# USBc_to_Ethernet_2_0.net
KiCad netlist of a schematic drawn in Altium Designer
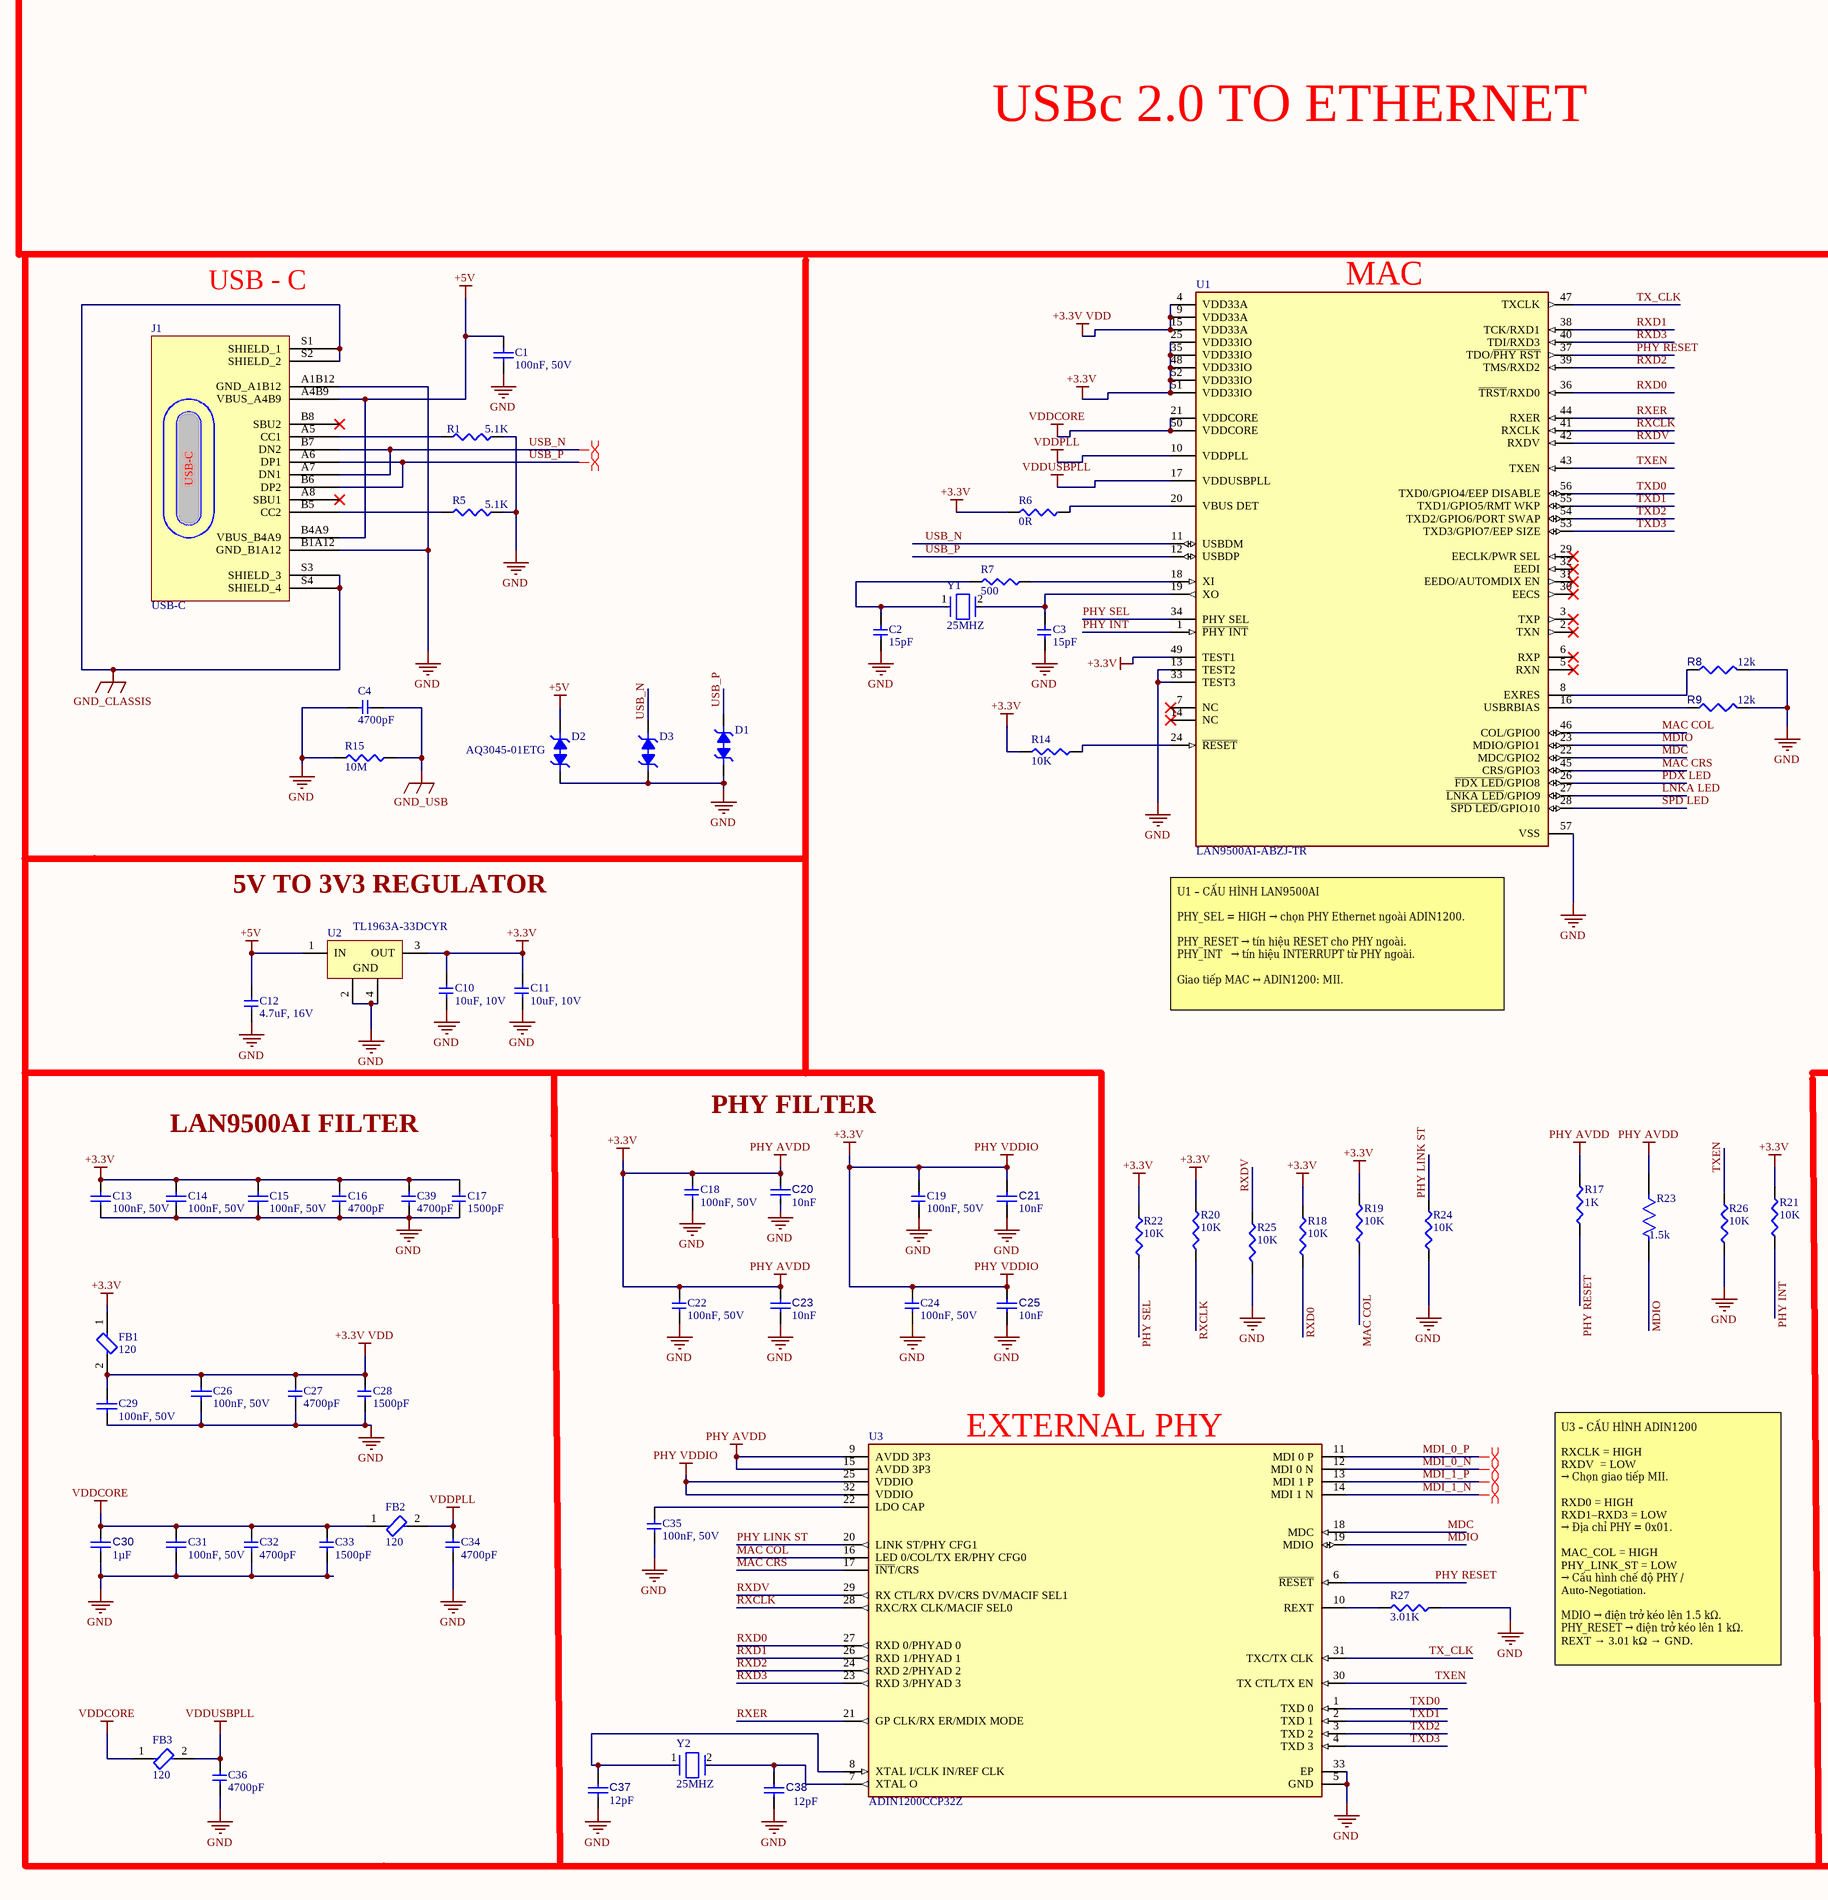
[diagram p0: USBc to Ethernet(2.0).SchDoc, left]
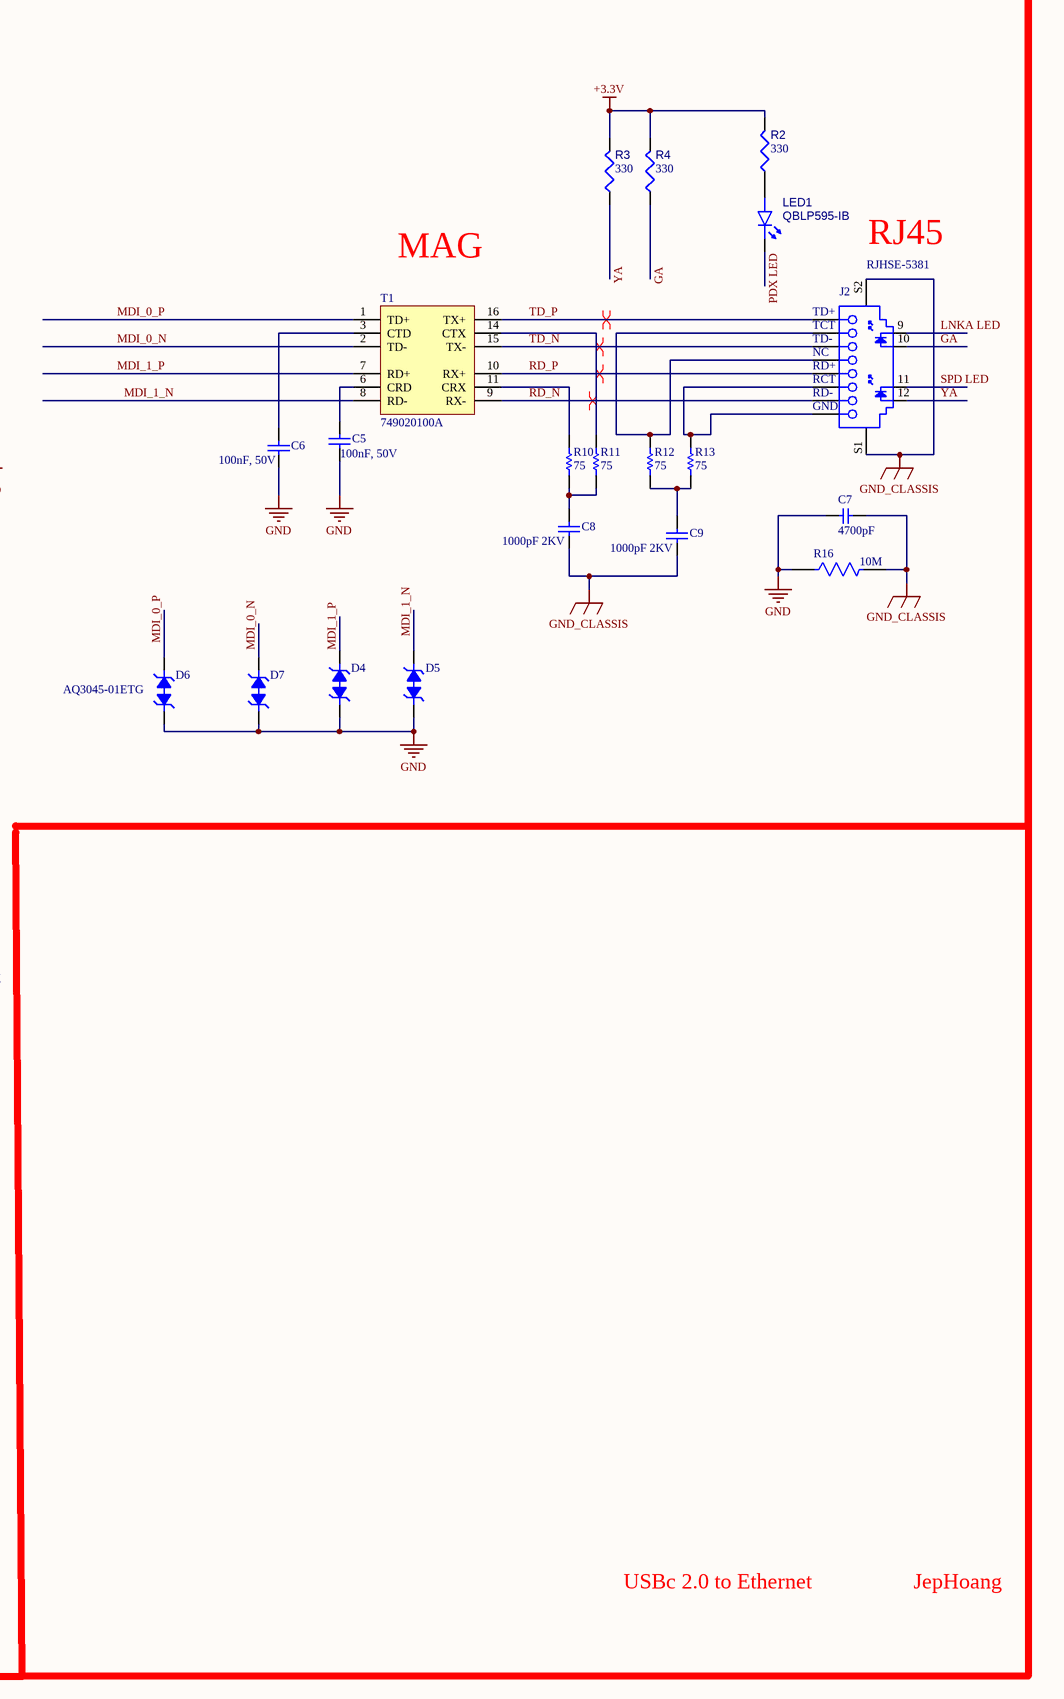
[diagram p1: USBc to Ethernet(2.0).SchDoc, right]

(export (version "E")
  (design (tool "Eeschema 10.0.6"))
  (components
    (comp (ref "C1")
      (value "100nF, 50V")
      (footprint "CAP_0402")
      (description "CAP CER 0.1UF 50V X7R 0402")
      (fields
        (field (name "MANUFACTURER") "Samsung")
        (field (name "MANUFACTURER PART NUMBER") "CL05B104KB54PNC")
      )
      (libsource (lib "HIEPSchlib") (part "CL05B104KB54PNC"))
    )
    (comp (ref "C2")
      (value "15pF")
      (footprint "CAP_0402")
      (description "Multilayer Ceramic Capacitors MLCC - SMD/SMT 0402 C0G 15pF 5% 100V automotive grade")
      (fields
        (field (name "MANUFACTURER") "Samsung Electro-Mechanics")
        (field (name "MANUFACTURER PART NUMBER") "CL05C150JC51PNC")
      )
      (libsource (lib "HIEPSchlib") (part "CL05C150JC51PNC"))
    )
    (comp (ref "C3")
      (value "15pF")
      (footprint "CAP_0402")
      (description "Multilayer Ceramic Capacitors MLCC - SMD/SMT 0402 C0G 15pF 5% 100V automotive grade")
      (fields
        (field (name "MANUFACTURER") "Samsung Electro-Mechanics")
        (field (name "MANUFACTURER PART NUMBER") "CL05C150JC51PNC")
      )
      (libsource (lib "HIEPSchlib") (part "CL05C150JC51PNC"))
    )
    (comp (ref "C4")
      (value "4700pF")
      (footprint "CAP_0402")
      (description "4700 pF ±10% 50V Ceramic Capacitor X7R 0402 (1005 Metric)")
      (fields
        (field (name "MANUFACTURER") "Samsung Electro-Mechanics")
        (field (name "MANUFACTURER PART NUMBER") "CL05B472KB5NNNC")
      )
      (libsource (lib "HIEPSchlib") (part "CL05B472KB5NNNC"))
    )
    (comp (ref "C5")
      (value "100nF, 50V")
      (footprint "CAP_0402")
      (description "CAP CER 0.1UF 50V X7R 0402")
      (fields
        (field (name "MANUFACTURER") "Samsung")
        (field (name "MANUFACTURER PART NUMBER") "CL05B104KB54PNC")
      )
      (libsource (lib "HIEPSchlib") (part "CL05B104KB54PNC"))
    )
    (comp (ref "C6")
      (value "100nF, 50V")
      (footprint "CAP_0402")
      (description "CAP CER 0.1UF 50V X7R 0402")
      (fields
        (field (name "MANUFACTURER") "Samsung")
        (field (name "MANUFACTURER PART NUMBER") "CL05B104KB54PNC")
      )
      (libsource (lib "HIEPSchlib") (part "CL05B104KB54PNC"))
    )
    (comp (ref "C7")
      (value "4700pF")
      (footprint "CAP_0402")
      (description "4700 pF ±10% 50V Ceramic Capacitor X7R 0402 (1005 Metric)")
      (fields
        (field (name "MANUFACTURER") "Samsung Electro-Mechanics")
        (field (name "MANUFACTURER PART NUMBER") "CL05B472KB5NNNC")
      )
      (libsource (lib "HIEPSchlib") (part "CL05B472KB5NNNC"))
    )
    (comp (ref "C8")
      (value "1000pF 2KV")
      (footprint "JD-202R18W102KV4E-2_M")
      (description "Chip Capacitor, 1 nF, +/- 10%, 2000 V, -55 to 125 degC, 1206 (3216 Metric), RoHS, Tape and Reel")
      (fields (field (name "MANUFACTURER") "Johanson Dielectrics") (field (name "TOLERANCE") "10%"))
      (libsource (lib "Altium Content Vault") (part "CAP-NP-2"))
    )
    (comp (ref "C9")
      (value "1000pF 2KV")
      (footprint "JD-202R18W102KV4E-2_M")
      (description "Chip Capacitor, 1 nF, +/- 10%, 2000 V, -55 to 125 degC, 1206 (3216 Metric), RoHS, Tape and Reel")
      (fields (field (name "MANUFACTURER") "Johanson Dielectrics") (field (name "TOLERANCE") "10%"))
      (libsource (lib "Altium Content Vault") (part "CAP-NP-2"))
    )
    (comp (ref "C10")
      (value "10uF, 10V")
      (footprint "CAP_0402")
      (description "CAP CER 10UF 10V X5R 0402")
      (fields
        (field (name "MANUFACTURER") "Samsung Electro-Mechanics")
        (field (name "MANUFACTURER PART NUMBER") "CL05A106MP5NUNC")
      )
      (libsource (lib "HIEPSchlib") (part "CL05A106MP5NUNC"))
    )
    (comp (ref "C11")
      (value "10uF, 10V")
      (footprint "CAP_0402")
      (description "CAP CER 10UF 10V X5R 0402")
      (fields
        (field (name "MANUFACTURER") "Samsung Electro-Mechanics")
        (field (name "MANUFACTURER PART NUMBER") "CL05A106MP5NUNC")
      )
      (libsource (lib "HIEPSchlib") (part "CL05A106MP5NUNC"))
    )
    (comp (ref "C12")
      (value "4.7uF, 16V")
      (footprint "CAP_0402")
      (description "CAP CER 4.7UF 16V X5R 0402")
      (fields
        (field (name "MANUFACTURER") "Samsung Electro-Mechanics")
        (field (name "MANUFACTURER PART NUMBER") "CL05A475MO5NUNC")
      )
      (libsource (lib "HIEPSchlib") (part "CL05A475MO5NUNC"))
    )
    (comp (ref "C13")
      (value "100nF, 50V")
      (footprint "CAP_0402")
      (description "CAP CER 0.1UF 50V X7R 0402")
      (fields
        (field (name "MANUFACTURER") "Samsung")
        (field (name "MANUFACTURER PART NUMBER") "CL05B104KB54PNC")
      )
      (libsource (lib "HIEPSchlib") (part "CL05B104KB54PNC"))
    )
    (comp (ref "C14")
      (value "100nF, 50V")
      (footprint "CAP_0402")
      (description "CAP CER 0.1UF 50V X7R 0402")
      (fields
        (field (name "MANUFACTURER") "Samsung")
        (field (name "MANUFACTURER PART NUMBER") "CL05B104KB54PNC")
      )
      (libsource (lib "HIEPSchlib") (part "CL05B104KB54PNC"))
    )
    (comp (ref "C15")
      (value "100nF, 50V")
      (footprint "CAP_0402")
      (description "CAP CER 0.1UF 50V X7R 0402")
      (fields
        (field (name "MANUFACTURER") "Samsung")
        (field (name "MANUFACTURER PART NUMBER") "CL05B104KB54PNC")
      )
      (libsource (lib "HIEPSchlib") (part "CL05B104KB54PNC"))
    )
    (comp (ref "C16")
      (value "4700pF")
      (footprint "CAP_0402")
      (description "4700 pF ±10% 50V Ceramic Capacitor X7R 0402 (1005 Metric)")
      (fields
        (field (name "MANUFACTURER") "Samsung Electro-Mechanics")
        (field (name "MANUFACTURER PART NUMBER") "CL05B472KB5NNNC")
      )
      (libsource (lib "HIEPSchlib") (part "CL05B472KB5NNNC"))
    )
    (comp (ref "C17")
      (value "1500pF")
      (footprint "CAP_0402")
      (description "1500 pF ±10% 50V Ceramic Capacitor X7R 0402 (1005 Metric)")
      (fields
        (field (name "MANUFACTURER") "Samsung Electro-Mechanics")
        (field (name "MANUFACTURER PART NUMBER") "CL05B152KB5VPNC")
      )
      (libsource (lib "HIEPSchlib") (part "CL05B152KB5VPNC"))
    )
    (comp (ref "C18")
      (value "100nF, 50V")
      (footprint "CAP_0402")
      (description "Multilayer Ceramic Capacitors MLCC - SMD/SMT 100nF0.150V X7R 1005 0402")
      (fields
        (field (name "MANUFACTURER") "Samsung Electro-Mechanics")
        (field (name "MANUFACTURER PART NUMBER") "CL05B104KB5NNNC")
      )
      (libsource (lib "HIEPSchlib") (part "CL05B104KB5NNNC"))
    )
    (comp (ref "C19")
      (value "100nF, 50V")
      (footprint "CAP_0402")
      (description "Multilayer Ceramic Capacitors MLCC - SMD/SMT 100nF0.150V X7R 1005 0402")
      (fields
        (field (name "MANUFACTURER") "Samsung Electro-Mechanics")
        (field (name "MANUFACTURER PART NUMBER") "CL05B104KB5NNNC")
      )
      (libsource (lib "HIEPSchlib") (part "CL05B104KB5NNNC"))
    )
    (comp (ref "C20")
      (value "10nF")
      (footprint "CAPC0402(1005)60_L")
      (description "Chip Capacitor, 10nF +/-20%, 50V, 0402, Thickness 0.6 mm")
      (fields (field (name "TOLERANCE") "5%") (field (name "Comment") "Capacitor 10nF +/-20% 50V 0402"))
      (libsource (lib "Hiep Hoang") (part "CAP-NP-2"))
    )
    (comp (ref "C21")
      (value "10nF")
      (footprint "CAPC0402(1005)60_L")
      (description "Chip Capacitor, 10nF +/-20%, 50V, 0402, Thickness 0.6 mm")
      (fields (field (name "TOLERANCE") "5%") (field (name "Comment") "Capacitor 10nF +/-20% 50V 0402"))
      (libsource (lib "Hiep Hoang") (part "CAP-NP-2"))
    )
    (comp (ref "C22")
      (value "100nF, 50V")
      (footprint "CAP_0402")
      (description "Multilayer Ceramic Capacitors MLCC - SMD/SMT 100nF0.150V X7R 1005 0402")
      (fields
        (field (name "MANUFACTURER") "Samsung Electro-Mechanics")
        (field (name "MANUFACTURER PART NUMBER") "CL05B104KB5NNNC")
      )
      (libsource (lib "HIEPSchlib") (part "CL05B104KB5NNNC"))
    )
    (comp (ref "C23")
      (value "10nF")
      (footprint "CAPC0402(1005)60_L")
      (description "Chip Capacitor, 10nF +/-20%, 50V, 0402, Thickness 0.6 mm")
      (fields (field (name "TOLERANCE") "5%") (field (name "Comment") "Capacitor 10nF +/-20% 50V 0402"))
      (libsource (lib "Hiep Hoang") (part "CAP-NP-2"))
    )
    (comp (ref "C24")
      (value "100nF, 50V")
      (footprint "CAP_0402")
      (description "Multilayer Ceramic Capacitors MLCC - SMD/SMT 100nF0.150V X7R 1005 0402")
      (fields
        (field (name "MANUFACTURER") "Samsung Electro-Mechanics")
        (field (name "MANUFACTURER PART NUMBER") "CL05B104KB5NNNC")
      )
      (libsource (lib "HIEPSchlib") (part "CL05B104KB5NNNC"))
    )
    (comp (ref "C25")
      (value "10nF")
      (footprint "CAPC0402(1005)60_L")
      (description "Chip Capacitor, 10nF +/-20%, 50V, 0402, Thickness 0.6 mm")
      (fields (field (name "TOLERANCE") "5%") (field (name "Comment") "Capacitor 10nF +/-20% 50V 0402"))
      (libsource (lib "Hiep Hoang") (part "CAP-NP-2"))
    )
    (comp (ref "C26")
      (value "100nF, 50V")
      (footprint "CAP_0402")
      (description "CAP CER 0.1UF 50V X7R 0402")
      (fields
        (field (name "MANUFACTURER") "Samsung")
        (field (name "MANUFACTURER PART NUMBER") "CL05B104KB54PNC")
      )
      (libsource (lib "HIEPSchlib") (part "CL05B104KB54PNC"))
    )
    (comp (ref "C27")
      (value "4700pF")
      (footprint "CAP_0402")
      (description "4700 pF ±10% 50V Ceramic Capacitor X7R 0402 (1005 Metric)")
      (fields
        (field (name "MANUFACTURER") "Samsung Electro-Mechanics")
        (field (name "MANUFACTURER PART NUMBER") "CL05B472KB5NNNC")
      )
      (libsource (lib "HIEPSchlib") (part "CL05B472KB5NNNC"))
    )
    (comp (ref "C28")
      (value "1500pF")
      (footprint "CAP_0402")
      (description "1500 pF ±10% 50V Ceramic Capacitor X7R 0402 (1005 Metric)")
      (fields
        (field (name "MANUFACTURER") "Samsung Electro-Mechanics")
        (field (name "MANUFACTURER PART NUMBER") "CL05B152KB5VPNC")
      )
      (libsource (lib "HIEPSchlib") (part "CL05B152KB5VPNC"))
    )
    (comp (ref "C29")
      (value "100nF, 50V")
      (footprint "CAP_0402")
      (description "CAP CER 0.1UF 50V X7R 0402")
      (fields
        (field (name "MANUFACTURER") "Samsung")
        (field (name "MANUFACTURER PART NUMBER") "CL05B104KB54PNC")
      )
      (libsource (lib "HIEPSchlib") (part "CL05B104KB54PNC"))
    )
    (comp (ref "C30")
      (value "1µF")
      (footprint "CAPC0402(1005)60_L")
      (description "Chip Capacitor, 1µF +/-20%, 10V, 0402, Thickness 0.6 mm")
      (fields (field (name "TOLERANCE") "10%") (field (name "Comment") "Capacitor 1µF +/-20% 10V 0402"))
      (libsource (lib "Hiep Hoang") (part "CAP-NP-2"))
    )
    (comp (ref "C31")
      (value "100nF, 50V")
      (footprint "CAP_0402")
      (description "CAP CER 0.1UF 50V X7R 0402")
      (fields
        (field (name "MANUFACTURER") "Samsung")
        (field (name "MANUFACTURER PART NUMBER") "CL05B104KB54PNC")
      )
      (libsource (lib "HIEPSchlib") (part "CL05B104KB54PNC"))
    )
    (comp (ref "C32")
      (value "4700pF")
      (footprint "CAP_0402")
      (description "4700 pF ±10% 50V Ceramic Capacitor X7R 0402 (1005 Metric)")
      (fields
        (field (name "MANUFACTURER") "Samsung Electro-Mechanics")
        (field (name "MANUFACTURER PART NUMBER") "CL05B472KB5NNNC")
      )
      (libsource (lib "HIEPSchlib") (part "CL05B472KB5NNNC"))
    )
    (comp (ref "C33")
      (value "1500pF")
      (footprint "CAP_0402")
      (description "1500 pF ±10% 50V Ceramic Capacitor X7R 0402 (1005 Metric)")
      (fields
        (field (name "MANUFACTURER") "Samsung Electro-Mechanics")
        (field (name "MANUFACTURER PART NUMBER") "CL05B152KB5VPNC")
      )
      (libsource (lib "HIEPSchlib") (part "CL05B152KB5VPNC"))
    )
    (comp (ref "C34")
      (value "4700pF")
      (footprint "CAP_0402")
      (description "4700 pF ±10% 50V Ceramic Capacitor X7R 0402 (1005 Metric)")
      (fields
        (field (name "MANUFACTURER") "Samsung Electro-Mechanics")
        (field (name "MANUFACTURER PART NUMBER") "CL05B472KB5NNNC")
      )
      (libsource (lib "HIEPSchlib") (part "CL05B472KB5NNNC"))
    )
    (comp (ref "C35")
      (value "100nF, 50V")
      (footprint "CAP_0402")
      (description "Multilayer Ceramic Capacitors MLCC - SMD/SMT 100nF0.150V X7R 1005 0402")
      (fields
        (field (name "MANUFACTURER") "Samsung Electro-Mechanics")
        (field (name "MANUFACTURER PART NUMBER") "CL05B104KB5NNNC")
      )
      (libsource (lib "HIEPSchlib") (part "CL05B104KB5NNNC"))
    )
    (comp (ref "C36")
      (value "4700pF")
      (footprint "CAP_0402")
      (description "4700 pF ±10% 50V Ceramic Capacitor X7R 0402 (1005 Metric)")
      (fields
        (field (name "MANUFACTURER") "Samsung Electro-Mechanics")
        (field (name "MANUFACTURER PART NUMBER") "CL05B472KB5NNNC")
      )
      (libsource (lib "HIEPSchlib") (part "CL05B472KB5NNNC"))
    )
    (comp (ref "C37")
      (value "12pF")
      (footprint "CAPC0402(1005)33_L")
      (description "Chip Capacitor, 12pF +/-10%, 50V, 0402, Thickness 0.33 mm")
      (fields (field (name "TOLERANCE") "20%") (field (name "Comment") "Capacitor 12pF +/-10% 50V 0402"))
      (libsource (lib "Hiep Hoang") (part "CAP-NP-2"))
    )
    (comp (ref "C38")
      (value "12pF")
      (footprint "CAPC0402(1005)33_L")
      (description "Chip Capacitor, 12pF +/-10%, 50V, 0402, Thickness 0.33 mm")
      (fields (field (name "TOLERANCE") "20%") (field (name "Comment") "Capacitor 12pF +/-10% 50V 0402"))
      (libsource (lib "Hiep Hoang") (part "CAP-NP-2"))
    )
    (comp (ref "C39")
      (value "4700pF")
      (footprint "CAP_0402")
      (description "4700 pF ±10% 50V Ceramic Capacitor X7R 0402 (1005 Metric)")
      (fields
        (field (name "MANUFACTURER") "Samsung Electro-Mechanics")
        (field (name "MANUFACTURER PART NUMBER") "CL05B472KB5NNNC")
      )
      (libsource (lib "HIEPSchlib") (part "CL05B472KB5NNNC"))
    )
    (comp (ref "D1")
      (value "~")
      (footprint "DIODE_0402")
      (description "TVS DIODE 5.3VWM 12VC SOD882")
      (fields
        (field (name "MANUFACTURER") "Littelfuse")
        (field (name "MANUFACTURER PART NUMBER") "AQ3045-01ETG")
      )
      (libsource (lib "HIEPSchlib") (part "AQ3045-01ETG"))
    )
    (comp (ref "D2")
      (value "AQ3045-01ETG")
      (footprint "DIODE_0402")
      (description "TVS DIODE 5.3VWM 12VC SOD882")
      (fields (field (name "MANUFACTURER") "Littelfuse") (field (name "LCSC PART NUMBER") "C3710326"))
      (libsource (lib "HIEPSchlib") (part "AQ3045-01ETG"))
    )
    (comp (ref "D3")
      (value "~")
      (footprint "DIODE_0402")
      (description "TVS DIODE 5.3VWM 12VC SOD882")
      (fields
        (field (name "MANUFACTURER") "Littelfuse")
        (field (name "MANUFACTURER PART NUMBER") "AQ3045-01ETG")
      )
      (libsource (lib "HIEPSchlib") (part "AQ3045-01ETG"))
    )
    (comp (ref "D4")
      (value "~")
      (footprint "DIODE_0402")
      (description "TVS DIODE 5.3VWM 12VC SOD882")
      (fields
        (field (name "MANUFACTURER") "Littelfuse")
        (field (name "MANUFACTURER PART NUMBER") "AQ3045-01ETG")
      )
      (libsource (lib "HIEPSchlib") (part "AQ3045-01ETG"))
    )
    (comp (ref "D5")
      (value "~")
      (footprint "DIODE_0402")
      (description "TVS DIODE 5.3VWM 12VC SOD882")
      (fields
        (field (name "MANUFACTURER") "Littelfuse")
        (field (name "MANUFACTURER PART NUMBER") "AQ3045-01ETG")
      )
      (libsource (lib "HIEPSchlib") (part "AQ3045-01ETG"))
    )
    (comp (ref "D6")
      (value "AQ3045-01ETG")
      (footprint "DIODE_0402")
      (description "TVS DIODE 5.3VWM 12VC SOD882")
      (fields (field (name "MANUFACTURER") "Littelfuse") (field (name "LCSC PART NUMBER") "C3710326"))
      (libsource (lib "HIEPSchlib") (part "AQ3045-01ETG"))
    )
    (comp (ref "D7")
      (value "~")
      (footprint "DIODE_0402")
      (description "TVS DIODE 5.3VWM 12VC SOD882")
      (fields
        (field (name "MANUFACTURER") "Littelfuse")
        (field (name "MANUFACTURER PART NUMBER") "AQ3045-01ETG")
      )
      (libsource (lib "HIEPSchlib") (part "AQ3045-01ETG"))
    )
    (comp (ref "FB1")
      (value "120")
      (footprint "RES_0603")
      (description "FERRITE BEAD 120 OHM 0603 1LN")
      (fields
        (field (name "MANUFACTURER") "TDK")
        (field (name "MANUFACTURER PART NUMBER") "MMZ1608B121CTAH0")
      )
      (libsource (lib "HIEPSchlib") (part "MMZ1608B121CTAH0"))
    )
    (comp (ref "FB2")
      (value "120")
      (footprint "RES_0603")
      (description "FERRITE BEAD 120 OHM 0603 1LN")
      (fields
        (field (name "MANUFACTURER") "TDK")
        (field (name "MANUFACTURER PART NUMBER") "MMZ1608B121CTAH0")
      )
      (libsource (lib "HIEPSchlib") (part "MMZ1608B121CTAH0"))
    )
    (comp (ref "FB3")
      (value "120")
      (footprint "RES_0603")
      (description "FERRITE BEAD 120 OHM 0603 1LN")
      (fields
        (field (name "MANUFACTURER") "TDK")
        (field (name "MANUFACTURER PART NUMBER") "MMZ1608B121CTAH0")
      )
      (libsource (lib "HIEPSchlib") (part "MMZ1608B121CTAH0"))
    )
    (comp (ref "J1")
      (value "USB-C")
      (footprint "USBc_16PIN_QFN__footprint")
      (fields (field (name "MANUFACTURER") "Molex") (field (name "MANUFACTURER PART NUMBER") "217179-0001"))
      (libsource (lib "HIEPSchlib") (part "217179-0001"))
    )
    (comp (ref "J2")
      (value "RJHSE-5381")
      (footprint "AMPH-RJHSE-5381_V")
      (fields (field (name "MANUFACTURER") "Amphenol"))
      (libsource (lib "Altium Content Vault") (part "RJ45-12-2SHLD"))
    )
    (comp (ref "LED1")
      (value "QBLP595-IB")
      (footprint "QTB-QBLP595_V")
      (description "Chip LED 0402, Blue, 0.02 A, 3.1 to 3.7 V, -40 to 80 degC, 2-Pin SMD, RoHS, Tape and Reel")
      (libsource (lib "Hiep Hoang") (part "LED-KA-2"))
    )
    (comp (ref "R1")
      (value "5.1K")
      (footprint "RES_0402")
      (fields
        (field (name "MANUFACTURER") "Yageo Group")
        (field (name "MANUFACTURER PART NUMBER") "AF0402FR-075K1L")
        (field (name "TOLERANCE") "1%")
      )
      (libsource (lib "HIEPSchlib") (part "AF0402FR-075K1L"))
    )
    (comp (ref "R2")
      (value "330")
      (footprint "RESC0402(1005)_L")
      (description "Chip Resistor, 330 Ohms, +/-5 %, 63 mW, -55 to 155 degC, 0402")
      (fields (field (name "POWER") "63mW") (field (name "TOLERANCE") "5%"))
      (libsource (lib "Hiep Hoang") (part "RES-2"))
    )
    (comp (ref "R3")
      (value "330")
      (footprint "RESC0402(1005)_L")
      (description "Chip Resistor, 330 Ohms, +/-5 %, 63 mW, -55 to 155 degC, 0402")
      (fields (field (name "POWER") "63mW") (field (name "TOLERANCE") "5%"))
      (libsource (lib "Hiep Hoang") (part "RES-2"))
    )
    (comp (ref "R4")
      (value "330")
      (footprint "RESC0402(1005)_L")
      (description "Chip Resistor, 330 Ohms, +/-5 %, 63 mW, -55 to 155 degC, 0402")
      (fields (field (name "POWER") "63mW") (field (name "TOLERANCE") "5%"))
      (libsource (lib "Hiep Hoang") (part "RES-2"))
    )
    (comp (ref "R5")
      (value "5.1K")
      (footprint "RES_0402")
      (fields
        (field (name "MANUFACTURER") "Yageo Group")
        (field (name "MANUFACTURER PART NUMBER") "AF0402FR-075K1L")
        (field (name "TOLERANCE") "1%")
      )
      (libsource (lib "HIEPSchlib") (part "AF0402FR-075K1L"))
    )
    (comp (ref "R6")
      (value "0R")
      (footprint "RES_0402")
      (description "RES 0 OHM JUMPER 1/16W 0402")
      (fields
        (field (name "MANUFACTURER") "Yageo")
        (field (name "MANUFACTURER PART NUMBER") "RC0402JR-070RL")
      )
      (libsource (lib "HIEPSchlib") (part "RC0402JR-070RL"))
    )
    (comp (ref "R7")
      (value "500")
      (footprint "RES_0402")
      (description "500 Ohms 1% 0.063W, 1/16W Chip Resistor 0402 (1005 Metric) Moisture Resistant")
      (fields
        (field (name "MANUFACTURER") "Yageo Group")
        (field (name "MANUFACTURER PART NUMBER") "RT0402FRE07500RL")
      )
      (libsource (lib "HIEPSchlib") (part "RT0402FRE07500RL"))
    )
    (comp (ref "R8")
      (value "12k")
      (footprint "RESC0402(1005)_L")
      (description "12K 0.063W 1% 0402 (1005 Metric)  SMD")
      (fields (field (name "TOLERANCE") "1%") (field (name "POWER") "63mW"))
      (libsource (lib "Hiep Hoang") (part "12KR2F"))
    )
    (comp (ref "R9")
      (value "12k")
      (footprint "RESC0402(1005)_L")
      (description "12K 0.063W 1% 0402 (1005 Metric)  SMD")
      (fields (field (name "TOLERANCE") "1%") (field (name "POWER") "63mW"))
      (libsource (lib "Hiep Hoang") (part "12KR2F"))
    )
    (comp (ref "R10")
      (value "75")
      (footprint "RESC1005X40X25LL05T10")
      (fields (field (name "MANUFACTURER") "Yageo / Phycomp") (field (name "PART NUMBER") "RC0402FR-0775RL"))
      (libsource (lib "Altium Content Vault") (part "RES"))
    )
    (comp (ref "R11")
      (value "75")
      (footprint "RESC1005X40X25LL05T10")
      (fields (field (name "MANUFACTURER") "Yageo / Phycomp") (field (name "PART NUMBER") "RC0402FR-0775RL"))
      (libsource (lib "Altium Content Vault") (part "RES"))
    )
    (comp (ref "R12")
      (value "75")
      (footprint "RESC1005X40X25LL05T10")
      (fields (field (name "MANUFACTURER") "Yageo / Phycomp") (field (name "PART NUMBER") "RC0402FR-0775RL"))
      (libsource (lib "Altium Content Vault") (part "RES"))
    )
    (comp (ref "R13")
      (value "75")
      (footprint "RESC1005X40X25LL05T10")
      (fields (field (name "MANUFACTURER") "Yageo / Phycomp") (field (name "PART NUMBER") "RC0402FR-0775RL"))
      (libsource (lib "Altium Content Vault") (part "RES"))
    )
    (comp (ref "R14")
      (value "10K")
      (footprint "RES_0402")
      (description "RES SMD 10K OHM 1% 1/16W 0402")
      (fields
        (field (name "MANUFACTURER") "Yageo Group")
        (field (name "MANUFACTURER PART NUMBER") "AC0402FR-0710KL")
      )
      (libsource (lib "HIEPSchlib") (part "AC0402FR-0710KL"))
    )
    (comp (ref "R15")
      (value "10M")
      (footprint "RES_0603")
      (description "Res Thick Film 0603 10M Ohm 1% 0.1W(1/10W) ±100ppm/C Pad SMD T/R Automotive AEC-Q200")
      (fields
        (field (name "MANUFACTURER") "Yageo Group")
        (field (name "MANUFACTURER PART NUMBER") "AC0603FR-0710ML")
      )
      (libsource (lib "HIEPSchlib") (part "AC0603FR-0710ML"))
    )
    (comp (ref "R16")
      (value "10M")
      (footprint "FP-CRCW0603-e3-IPC_A")
      (description "RES Thick Film, 10MΩ, 1%, 0.1W, 100ppm/°C, 0603")
      (fields (field (name "TOLERANCE") "1%"))
      (libsource (lib "Altium Content Vault") (part "1029c3af85768c4190bb7ad29bc67b5"))
    )
    (comp (ref "R17")
      (value "1K")
      (footprint "RES_0402")
      (description "RES 1K OHM 1% 1/16W 0402")
      (fields
        (field (name "MANUFACTURER") "Yageo")
        (field (name "MANUFACTURER PART NUMBER") "RC0402FR-071KL")
      )
      (libsource (lib "HIEPSchlib") (part "RC0402FR-071KL"))
    )
    (comp (ref "R18")
      (value "10K")
      (footprint "RES_0402")
      (description "RES SMD 10K OHM 1% 1/16W 0402")
      (fields
        (field (name "MANUFACTURER") "Yageo Group")
        (field (name "MANUFACTURER PART NUMBER") "AC0402FR-0710KL")
      )
      (libsource (lib "HIEPSchlib") (part "AC0402FR-0710KL"))
    )
    (comp (ref "R19")
      (value "10K")
      (footprint "RES_0402")
      (description "RES SMD 10K OHM 1% 1/16W 0402")
      (fields
        (field (name "MANUFACTURER") "Yageo Group")
        (field (name "MANUFACTURER PART NUMBER") "AC0402FR-0710KL")
      )
      (libsource (lib "HIEPSchlib") (part "AC0402FR-0710KL"))
    )
    (comp (ref "R20")
      (value "10K")
      (footprint "RES_0402")
      (description "RES SMD 10K OHM 1% 1/16W 0402")
      (fields
        (field (name "MANUFACTURER") "Yageo Group")
        (field (name "MANUFACTURER PART NUMBER") "AC0402FR-0710KL")
      )
      (libsource (lib "HIEPSchlib") (part "AC0402FR-0710KL"))
    )
    (comp (ref "R21")
      (value "10K")
      (footprint "RES_0402")
      (description "RES SMD 10K OHM 1% 1/16W 0402")
      (fields
        (field (name "MANUFACTURER") "Yageo Group")
        (field (name "MANUFACTURER PART NUMBER") "AC0402FR-0710KL")
      )
      (libsource (lib "HIEPSchlib") (part "AC0402FR-0710KL"))
    )
    (comp (ref "R22")
      (value "10K")
      (footprint "RES_0402")
      (description "RES SMD 10K OHM 1% 1/16W 0402")
      (fields
        (field (name "MANUFACTURER") "Yageo Group")
        (field (name "MANUFACTURER PART NUMBER") "AC0402FR-0710KL")
      )
      (libsource (lib "HIEPSchlib") (part "AC0402FR-0710KL"))
    )
    (comp (ref "R23")
      (value "1.5k")
      (footprint "FP-RT0402-MFG")
      (description "RES SMD 1.5K OHM 0.5% 1/16W 0402")
      (fields
        (field (name "OCTOPART") "https://octopart.com/rt0402drd071k5l-yageo-1260316")
        (field (name "MANUFACTURER") "Yageo")
      )
      (libsource (lib "Altium Content Vault") (part "1029c3af85768c4190bb7ad29bc67b5"))
    )
    (comp (ref "R24")
      (value "10K")
      (footprint "RES_0402")
      (description "RES SMD 10K OHM 1% 1/16W 0402")
      (fields
        (field (name "MANUFACTURER") "Yageo Group")
        (field (name "MANUFACTURER PART NUMBER") "AC0402FR-0710KL")
      )
      (libsource (lib "HIEPSchlib") (part "AC0402FR-0710KL"))
    )
    (comp (ref "R25")
      (value "10K")
      (footprint "RES_0402")
      (description "RES SMD 10K OHM 1% 1/16W 0402")
      (fields
        (field (name "MANUFACTURER") "Yageo Group")
        (field (name "MANUFACTURER PART NUMBER") "AC0402FR-0710KL")
      )
      (libsource (lib "HIEPSchlib") (part "AC0402FR-0710KL"))
    )
    (comp (ref "R26")
      (value "10K")
      (footprint "RES_0402")
      (description "RES SMD 10K OHM 1% 1/16W 0402")
      (fields
        (field (name "MANUFACTURER") "Yageo Group")
        (field (name "MANUFACTURER PART NUMBER") "AC0402FR-0710KL")
      )
      (libsource (lib "HIEPSchlib") (part "AC0402FR-0710KL"))
    )
    (comp (ref "R27")
      (value "3.01K")
      (footprint "RES_0402")
      (description "Res Thick Film 0402 3.01K Ohm 1% 1/16W ±100ppm/°C Molded SMD Paper T/R")
      (fields
        (field (name "MANUFACTURER") "Yageo Group")
        (field (name "MANUFACTURER PART NUMBER") "RC0402FR-073K01L")
      )
      (libsource (lib "HIEPSchlib") (part "RC0402FR-073K01L"))
    )
    (comp (ref "T1")
      (value "749020100A")
      (footprint "749020100A")
      (description "Xfmr, 10/100/1000 Base-T, 0.5 Port, Smd Rohs Compliant: Yes")
      (libsource (lib "Altium Content Vault") (part "749020100A"))
    )
    (comp (ref "U1")
      (value "LAN9500AI-ABZJ-TR")
      (footprint "FP-56QFN-5904-8x8B-MFG")
      (description "Ethernet Bridge, USB to Ethernet USB 2.0, 10/100 Base-T/TX PHY USB Interface 56-QFN (8x8)")
      (fields (field (name "MANUFACTURER") "Microchip"))
      (libsource (lib "USBc to Ethernet(2.0)") (part "LAN9500AI-ABZJ-TR"))
    )
    (comp (ref "U2")
      (value "TL1963A-33DCYR")
      (footprint "Regulator_4PIN")
      (description "IC REG LINEAR 3.3V 1.5A SOT223-4")
      (fields (field (name "MANUFACTURER") "Texas Instruments") (field (name "LCSC PART NUMBER") "C181262"))
      (libsource (lib "HIEPSchlib") (part "TL1963A-33DCYR_1"))
    )
    (comp (ref "U3")
      (value "ADIN1200CCP32Z")
      (footprint "FP-CP-32-31-MFG")
      (description "INDUSTRIAL ETHERNET GIGABIT PHY")
      (fields
        (field (name "OCTOPART") "https://octopart.com/adin1200ccp32z-analog+devices-103760365")
        (field (name "MANUFACTURER") "Analog Devices")
      )
      (libsource (lib "Altium Content Vault") (part "d941291fc6595d66c86e278ecb134d7"))
    )
    (comp (ref "Y1")
      (value "25MHZ")
      (footprint "Crystal_25MHZ")
      (description "Parallel - Fundamental Quartz Crystal, 25MHz Nom")
      (fields
        (field (name "MANUFACTURER") "CTS Components")
        (field (name "MANUFACTURER PART NUMBER") "445I23A25M00000")
      )
      (libsource (lib "HIEPSchlib") (part "445I23A25M00000"))
    )
    (comp (ref "Y2")
      (value "25MHZ")
      (footprint "Crystal_25MHZ")
      (description "Parallel - Fundamental Quartz Crystal, 25MHz Nom")
      (fields
        (field (name "MANUFACTURER") "CTS Components")
        (field (name "MANUFACTURER PART NUMBER") "445I23A25M00000")
      )
      (libsource (lib "HIEPSchlib") (part "445I23A25M00000"))
    )
  )
  (nets
    (net (code "1") (name "+3.3V") (class "Default")
      (node (ref "C10") (pin "2") (pinfunction "2_2") (pintype "passive"))
      (node (ref "C11") (pin "2") (pinfunction "2_2") (pintype "passive"))
      (node (ref "C13") (pin "2") (pinfunction "2_2") (pintype "passive"))
      (node (ref "C14") (pin "2") (pinfunction "2_2") (pintype "passive"))
      (node (ref "C15") (pin "2") (pinfunction "2_2") (pintype "passive"))
      (node (ref "C16") (pin "2") (pinfunction "2_2") (pintype "passive"))
      (node (ref "C17") (pin "2") (pinfunction "2_2") (pintype "passive"))
      (node (ref "C18") (pin "2") (pinfunction "2_2") (pintype "passive"))
      (node (ref "C19") (pin "2") (pinfunction "2_2") (pintype "passive"))
      (node (ref "C20") (pin "2") (pinfunction "2_2") (pintype "passive"))
      (node (ref "C21") (pin "2") (pinfunction "2_2") (pintype "passive"))
      (node (ref "C22") (pin "2") (pinfunction "2_2") (pintype "passive"))
      (node (ref "C23") (pin "2") (pinfunction "2_2") (pintype "passive"))
      (node (ref "C24") (pin "2") (pinfunction "2_2") (pintype "passive"))
      (node (ref "C25") (pin "2") (pinfunction "2_2") (pintype "passive"))
      (node (ref "C39") (pin "2") (pinfunction "2_2") (pintype "passive"))
      (node (ref "FB1") (pin "1") (pinfunction "1_1") (pintype "passive"))
      (node (ref "R14") (pin "2") (pinfunction "2_2") (pintype "passive"))
      (node (ref "R17") (pin "2") (pinfunction "2_2") (pintype "passive"))
      (node (ref "R18") (pin "2") (pinfunction "2_2") (pintype "passive"))
      (node (ref "R19") (pin "2") (pinfunction "2_2") (pintype "passive"))
      (node (ref "R2") (pin "2") (pinfunction "2_2") (pintype "passive"))
      (node (ref "R20") (pin "2") (pinfunction "2_2") (pintype "passive"))
      (node (ref "R21") (pin "2") (pinfunction "2_2") (pintype "passive"))
      (node (ref "R22") (pin "2") (pinfunction "2_2") (pintype "passive"))
      (node (ref "R23") (pin "1") (pinfunction "1_1") (pintype "passive"))
      (node (ref "R3") (pin "2") (pinfunction "2_2") (pintype "passive"))
      (node (ref "R4") (pin "2") (pinfunction "2_2") (pintype "passive"))
      (node (ref "R6") (pin "1") (pinfunction "1_1") (pintype "passive"))
      (node (ref "U1") (pin "25") (pinfunction "VDD33IO_25") (pintype "power_in"))
      (node (ref "U1") (pin "35") (pinfunction "VDD33IO_35") (pintype "power_in"))
      (node (ref "U1") (pin "48") (pinfunction "VDD33IO_48") (pintype "power_in"))
      (node (ref "U1") (pin "49") (pinfunction "TEST1_49") (pintype "passive"))
      (node (ref "U1") (pin "51") (pinfunction "VDD33IO_51") (pintype "power_in"))
      (node (ref "U1") (pin "52") (pinfunction "VDD33IO_52") (pintype "power_in"))
      (node (ref "U2") (pin "3") (pinfunction "OUT_3") (pintype "power_in"))
      (node (ref "U3") (pin "15") (pinfunction "AVDD_3P3_15") (pintype "power_in"))
      (node (ref "U3") (pin "25") (pinfunction "VDDIO_25") (pintype "power_in"))
      (node (ref "U3") (pin "32") (pinfunction "VDDIO_32") (pintype "power_in"))
      (node (ref "U3") (pin "9") (pinfunction "AVDD_3P3_9") (pintype "power_in"))
    )
    (net (code "2") (name "+3.3V VDD") (class "Default")
      (node (ref "C26") (pin "2") (pinfunction "2_2") (pintype "passive"))
      (node (ref "C27") (pin "2") (pinfunction "2_2") (pintype "passive"))
      (node (ref "C28") (pin "2") (pinfunction "2_2") (pintype "passive"))
      (node (ref "C29") (pin "2") (pinfunction "2_2") (pintype "passive"))
      (node (ref "FB1") (pin "2") (pinfunction "2_2") (pintype "passive"))
      (node (ref "U1") (pin "15") (pinfunction "VDD33A_15") (pintype "power_in"))
      (node (ref "U1") (pin "4") (pinfunction "VDD33A_4") (pintype "power_in"))
      (node (ref "U1") (pin "9") (pinfunction "VDD33A_9") (pintype "power_in"))
    )
    (net (code "3") (name "+5V") (class "Default")
      (node (ref "C1") (pin "2") (pinfunction "2_2") (pintype "passive"))
      (node (ref "C12") (pin "2") (pinfunction "2_2") (pintype "passive"))
      (node (ref "D2") (pin "2") (pinfunction "2_2") (pintype "passive"))
      (node (ref "J1") (pin "A4B9") (pinfunction "VBUS_A4B9_A4B9") (pintype "passive"))
      (node (ref "J1") (pin "B4A9") (pinfunction "VBUS_B4A9_B4A9") (pintype "passive"))
      (node (ref "U2") (pin "1") (pinfunction "IN_1") (pintype "power_in"))
    )
    (net (code "4") (name "/GA") (class "Default")
      (node (ref "J2") (pin "10") (pinfunction "10_10") (pintype "passive"))
      (node (ref "R4") (pin "1") (pinfunction "1_1") (pintype "passive"))
    )
    (net (code "5") (name "/LNKA LED") (class "Default")
      (node (ref "J2") (pin "9") (pinfunction "9_9") (pintype "passive"))
      (node (ref "U1") (pin "27") (pinfunction "~{LNKA_LED}/GPIO9_27") (pintype "bidirectional"))
    )
    (net (code "6") (name "/MAC COL") (class "Default")
      (node (ref "R19") (pin "1") (pinfunction "1_1") (pintype "passive"))
      (node (ref "U1") (pin "46") (pinfunction "COL/GPIO0_46") (pintype "bidirectional"))
      (node (ref "U3") (pin "16") (pinfunction "LED_0/COL/TX_ER/PHY_CFG0_16") (pintype "passive"))
    )
    (net (code "7") (name "/MAC CRS") (class "Default")
      (node (ref "U1") (pin "45") (pinfunction "CRS/GPIO3_45") (pintype "bidirectional"))
      (node (ref "U3") (pin "17") (pinfunction "~{INT}/CRS_17") (pintype "open_collector"))
    )
    (net (code "8") (name "/MDC") (class "Default")
      (node (ref "U1") (pin "22") (pinfunction "MDC/GPIO2_22") (pintype "bidirectional"))
      (node (ref "U3") (pin "18") (pinfunction "MDC_18") (pintype "input"))
    )
    (net (code "9") (name "/MDIO") (class "Default")
      (node (ref "R23") (pin "2") (pinfunction "2_2") (pintype "passive"))
      (node (ref "U1") (pin "23") (pinfunction "MDIO/GPIO1_23") (pintype "bidirectional"))
      (node (ref "U3") (pin "19") (pinfunction "MDIO_19") (pintype "bidirectional"))
    )
    (net (code "10") (name "/MDI_0_N") (class "Default")
      (node (ref "D7") (pin "2") (pinfunction "2_2") (pintype "passive"))
      (node (ref "T1") (pin "2") (pinfunction "TD-_2") (pintype "passive"))
      (node (ref "U3") (pin "12") (pinfunction "MDI_0_N_12") (pintype "passive"))
    )
    (net (code "11") (name "/MDI_0_P") (class "Default")
      (node (ref "D6") (pin "2") (pinfunction "2_2") (pintype "passive"))
      (node (ref "T1") (pin "1") (pinfunction "TD+_1") (pintype "passive"))
      (node (ref "U3") (pin "11") (pinfunction "MDI_0_P_11") (pintype "passive"))
    )
    (net (code "12") (name "/MDI_1_N") (class "Default")
      (node (ref "D5") (pin "2") (pinfunction "2_2") (pintype "passive"))
      (node (ref "T1") (pin "8") (pinfunction "RD-_8") (pintype "passive"))
      (node (ref "U3") (pin "14") (pinfunction "MDI_1_N_14") (pintype "passive"))
    )
    (net (code "13") (name "/MDI_1_P") (class "Default")
      (node (ref "D4") (pin "2") (pinfunction "2_2") (pintype "passive"))
      (node (ref "T1") (pin "7") (pinfunction "RD+_7") (pintype "passive"))
      (node (ref "U3") (pin "13") (pinfunction "MDI_1_P_13") (pintype "passive"))
    )
    (net (code "14") (name "/PDX LED") (class "Default")
      (node (ref "LED1") (pin "1") (pinfunction "K_1") (pintype "passive"))
      (node (ref "U1") (pin "26") (pinfunction "~{FDX_LED}/GPIO8_26") (pintype "bidirectional"))
    )
    (net (code "15") (name "/PHY INT") (class "Default")
      (node (ref "R21") (pin "1") (pinfunction "1_1") (pintype "passive"))
      (node (ref "U1") (pin "1") (pinfunction "~{PHY_INT}_1") (pintype "input"))
    )
    (net (code "16") (name "/PHY LINK ST") (class "Default")
      (node (ref "R24") (pin "2") (pinfunction "2_2") (pintype "passive"))
      (node (ref "U3") (pin "20") (pinfunction "LINK_ST/PHY_CFG1_20") (pintype "output"))
    )
    (net (code "17") (name "/PHY RESET") (class "Default")
      (node (ref "R17") (pin "1") (pinfunction "1_1") (pintype "passive"))
      (node (ref "U1") (pin "37") (pinfunction "TDO/~{PHY_RST}_37") (pintype "output"))
      (node (ref "U3") (pin "6") (pinfunction "~{RESET}_6") (pintype "input"))
    )
    (net (code "18") (name "/PHY SEL") (class "Default")
      (node (ref "R22") (pin "1") (pinfunction "1_1") (pintype "passive"))
      (node (ref "U1") (pin "34") (pinfunction "PHY_SEL_34") (pintype "passive"))
    )
    (net (code "19") (name "/RD_N") (class "Default")
      (node (ref "J2") (pin "7") (pinfunction "RD-_7") (pintype "passive"))
      (node (ref "T1") (pin "9") (pinfunction "RX-_9") (pintype "passive"))
    )
    (net (code "20") (name "/RD_P") (class "Default")
      (node (ref "J2") (pin "5") (pinfunction "RD+_5") (pintype "passive"))
      (node (ref "T1") (pin "10") (pinfunction "RX+_10") (pintype "passive"))
    )
    (net (code "21") (name "/RXCLK") (class "Default")
      (node (ref "R20") (pin "1") (pinfunction "1_1") (pintype "passive"))
      (node (ref "U1") (pin "41") (pinfunction "RXCLK_41") (pintype "input"))
      (node (ref "U3") (pin "28") (pinfunction "RXC/RX_CLK/MACIF_SEL0_28") (pintype "output"))
    )
    (net (code "22") (name "/RXD0") (class "Default")
      (node (ref "R18") (pin "1") (pinfunction "1_1") (pintype "passive"))
      (node (ref "U1") (pin "36") (pinfunction "~{TRST}/RXD0_36") (pintype "input"))
      (node (ref "U3") (pin "27") (pinfunction "RXD_0/PHYAD_0_27") (pintype "output"))
    )
    (net (code "23") (name "/RXD1") (class "Default")
      (node (ref "U1") (pin "38") (pinfunction "TCK/RXD1_38") (pintype "input"))
      (node (ref "U3") (pin "26") (pinfunction "RXD_1/PHYAD_1_26") (pintype "output"))
    )
    (net (code "24") (name "/RXD2") (class "Default")
      (node (ref "U1") (pin "39") (pinfunction "TMS/RXD2_39") (pintype "input"))
      (node (ref "U3") (pin "24") (pinfunction "RXD_2/PHYAD_2_24") (pintype "output"))
    )
    (net (code "25") (name "/RXD3") (class "Default")
      (node (ref "U1") (pin "40") (pinfunction "TDI/RXD3_40") (pintype "input"))
      (node (ref "U3") (pin "23") (pinfunction "RXD_3/PHYAD_3_23") (pintype "output"))
    )
    (net (code "26") (name "/RXDV") (class "Default")
      (node (ref "R25") (pin "2") (pinfunction "2_2") (pintype "passive"))
      (node (ref "U1") (pin "42") (pinfunction "RXDV_42") (pintype "input"))
      (node (ref "U3") (pin "29") (pinfunction "RX_CTL/RX_DV/CRS_DV/MACIF_SEL1_29") (pintype "output"))
    )
    (net (code "27") (name "/RXER") (class "Default")
      (node (ref "U1") (pin "44") (pinfunction "RXER_44") (pintype "input"))
      (node (ref "U3") (pin "21") (pinfunction "GP_CLK/RX_ER/MDIX_MODE_21") (pintype "output"))
    )
    (net (code "28") (name "/SPD LED") (class "Default")
      (node (ref "J2") (pin "11") (pinfunction "11_11") (pintype "passive"))
      (node (ref "U1") (pin "28") (pinfunction "~{SPD_LED}/GPIO10_28") (pintype "bidirectional"))
    )
    (net (code "29") (name "/TD_N") (class "Default")
      (node (ref "J2") (pin "3") (pinfunction "TD-_3") (pintype "passive"))
      (node (ref "T1") (pin "15") (pinfunction "TX-_15") (pintype "passive"))
    )
    (net (code "30") (name "/TD_P") (class "Default")
      (node (ref "J2") (pin "1") (pinfunction "TD+_1") (pintype "passive"))
      (node (ref "T1") (pin "16") (pinfunction "TX+_16") (pintype "passive"))
    )
    (net (code "31") (name "/TXD0") (class "Default")
      (node (ref "U1") (pin "56") (pinfunction "TXD0/GPIO4/EEP_DISABLE_56") (pintype "bidirectional"))
      (node (ref "U3") (pin "1") (pinfunction "TXD_0_1") (pintype "input"))
    )
    (net (code "32") (name "/TXD1") (class "Default")
      (node (ref "U1") (pin "55") (pinfunction "TXD1/GPIO5/RMT_WKP_55") (pintype "bidirectional"))
      (node (ref "U3") (pin "2") (pinfunction "TXD_1_2") (pintype "input"))
    )
    (net (code "33") (name "/TXD2") (class "Default")
      (node (ref "U1") (pin "54") (pinfunction "TXD2/GPIO6/PORT_SWAP_54") (pintype "bidirectional"))
      (node (ref "U3") (pin "3") (pinfunction "TXD_2_3") (pintype "input"))
    )
    (net (code "34") (name "/TXD3") (class "Default")
      (node (ref "U1") (pin "53") (pinfunction "TXD3/GPIO7/EEP_SIZE_53") (pintype "bidirectional"))
      (node (ref "U3") (pin "4") (pinfunction "TXD_3_4") (pintype "input"))
    )
    (net (code "35") (name "/TXEN") (class "Default")
      (node (ref "R26") (pin "2") (pinfunction "2_2") (pintype "passive"))
      (node (ref "U1") (pin "43") (pinfunction "TXEN_43") (pintype "input"))
      (node (ref "U3") (pin "30") (pinfunction "TX_CTL/TX_EN_30") (pintype "input"))
    )
    (net (code "36") (name "/TX_CLK") (class "Default")
      (node (ref "U1") (pin "47") (pinfunction "TXCLK_47") (pintype "output"))
      (node (ref "U3") (pin "31") (pinfunction "TXC/TX_CLK_31") (pintype "input"))
    )
    (net (code "37") (name "/USB_N") (class "Default")
      (node (ref "D3") (pin "2") (pinfunction "2_2") (pintype "passive"))
      (node (ref "J1") (pin "A7") (pinfunction "DN1_A7") (pintype "passive"))
      (node (ref "J1") (pin "B7") (pinfunction "DN2_B7") (pintype "passive"))
      (node (ref "U1") (pin "11") (pinfunction "USBDM_11") (pintype "bidirectional"))
    )
    (net (code "38") (name "/USB_P") (class "Default")
      (node (ref "D1") (pin "2") (pinfunction "2_2") (pintype "passive"))
      (node (ref "J1") (pin "A6") (pinfunction "DP1_A6") (pintype "passive"))
      (node (ref "J1") (pin "B6") (pinfunction "DP2_B6") (pintype "passive"))
      (node (ref "U1") (pin "12") (pinfunction "USBDP_12") (pintype "bidirectional"))
    )
    (net (code "39") (name "/YA") (class "Default")
      (node (ref "J2") (pin "12") (pinfunction "12_12") (pintype "passive"))
      (node (ref "R3") (pin "1") (pinfunction "1_1") (pintype "passive"))
    )
    (net (code "40") (name "GND") (class "Default")
      (node (ref "C1") (pin "1") (pinfunction "1_1") (pintype "passive"))
      (node (ref "C10") (pin "1") (pinfunction "1_1") (pintype "passive"))
      (node (ref "C11") (pin "1") (pinfunction "1_1") (pintype "passive"))
      (node (ref "C12") (pin "1") (pinfunction "1_1") (pintype "passive"))
      (node (ref "C13") (pin "1") (pinfunction "1_1") (pintype "passive"))
      (node (ref "C14") (pin "1") (pinfunction "1_1") (pintype "passive"))
      (node (ref "C15") (pin "1") (pinfunction "1_1") (pintype "passive"))
      (node (ref "C16") (pin "1") (pinfunction "1_1") (pintype "passive"))
      (node (ref "C17") (pin "1") (pinfunction "1_1") (pintype "passive"))
      (node (ref "C18") (pin "1") (pinfunction "1_1") (pintype "passive"))
      (node (ref "C19") (pin "1") (pinfunction "1_1") (pintype "passive"))
      (node (ref "C2") (pin "1") (pinfunction "1_1") (pintype "passive"))
      (node (ref "C20") (pin "1") (pinfunction "1_1") (pintype "passive"))
      (node (ref "C21") (pin "1") (pinfunction "1_1") (pintype "passive"))
      (node (ref "C22") (pin "1") (pinfunction "1_1") (pintype "passive"))
      (node (ref "C23") (pin "1") (pinfunction "1_1") (pintype "passive"))
      (node (ref "C24") (pin "1") (pinfunction "1_1") (pintype "passive"))
      (node (ref "C25") (pin "1") (pinfunction "1_1") (pintype "passive"))
      (node (ref "C26") (pin "1") (pinfunction "1_1") (pintype "passive"))
      (node (ref "C27") (pin "1") (pinfunction "1_1") (pintype "passive"))
      (node (ref "C28") (pin "1") (pinfunction "1_1") (pintype "passive"))
      (node (ref "C29") (pin "1") (pinfunction "1_1") (pintype "passive"))
      (node (ref "C3") (pin "1") (pinfunction "1_1") (pintype "passive"))
      (node (ref "C30") (pin "1") (pinfunction "1_1") (pintype "passive"))
      (node (ref "C31") (pin "1") (pinfunction "1_1") (pintype "passive"))
      (node (ref "C32") (pin "1") (pinfunction "1_1") (pintype "passive"))
      (node (ref "C33") (pin "1") (pinfunction "1_1") (pintype "passive"))
      (node (ref "C34") (pin "1") (pinfunction "1_1") (pintype "passive"))
      (node (ref "C35") (pin "1") (pinfunction "1_1") (pintype "passive"))
      (node (ref "C36") (pin "1") (pinfunction "1_1") (pintype "passive"))
      (node (ref "C37") (pin "2") (pinfunction "2_2") (pintype "passive"))
      (node (ref "C38") (pin "2") (pinfunction "2_2") (pintype "passive"))
      (node (ref "C39") (pin "1") (pinfunction "1_1") (pintype "passive"))
      (node (ref "C4") (pin "1") (pinfunction "1_1") (pintype "passive"))
      (node (ref "C5") (pin "1") (pinfunction "1_1") (pintype "passive"))
      (node (ref "C6") (pin "1") (pinfunction "1_1") (pintype "passive"))
      (node (ref "C7") (pin "2") (pinfunction "2_2") (pintype "passive"))
      (node (ref "D1") (pin "1") (pinfunction "1_1") (pintype "passive"))
      (node (ref "D2") (pin "1") (pinfunction "1_1") (pintype "passive"))
      (node (ref "D3") (pin "1") (pinfunction "1_1") (pintype "passive"))
      (node (ref "D4") (pin "1") (pinfunction "1_1") (pintype "passive"))
      (node (ref "D5") (pin "1") (pinfunction "1_1") (pintype "passive"))
      (node (ref "D6") (pin "1") (pinfunction "1_1") (pintype "passive"))
      (node (ref "D7") (pin "1") (pinfunction "1_1") (pintype "passive"))
      (node (ref "J1") (pin "A1B12") (pinfunction "GND_A1B12_A1B12") (pintype "passive"))
      (node (ref "J1") (pin "B1A12") (pinfunction "GND_B1A12_B1A12") (pintype "passive"))
      (node (ref "R1") (pin "2") (pinfunction "2_2") (pintype "passive"))
      (node (ref "R15") (pin "1") (pinfunction "1_1") (pintype "passive"))
      (node (ref "R16") (pin "1") (pinfunction "1_1") (pintype "passive"))
      (node (ref "R24") (pin "1") (pinfunction "1_1") (pintype "passive"))
      (node (ref "R25") (pin "1") (pinfunction "1_1") (pintype "passive"))
      (node (ref "R26") (pin "1") (pinfunction "1_1") (pintype "passive"))
      (node (ref "R27") (pin "2") (pinfunction "2_2") (pintype "passive"))
      (node (ref "R5") (pin "2") (pinfunction "2_2") (pintype "passive"))
      (node (ref "R8") (pin "2") (pinfunction "2_2") (pintype "passive"))
      (node (ref "R9") (pin "2") (pinfunction "2_2") (pintype "passive"))
      (node (ref "U1") (pin "13") (pinfunction "TEST2_13") (pintype "passive"))
      (node (ref "U1") (pin "33") (pinfunction "TEST3_33") (pintype "passive"))
      (node (ref "U1") (pin "57") (pinfunction "VSS_57") (pintype "power_in"))
      (node (ref "U2") (pin "2") (pinfunction "GND_2") (pintype "power_in"))
      (node (ref "U2") (pin "4") (pinfunction "GND_4") (pintype "power_in"))
      (node (ref "U3") (pin "33") (pinfunction "EP_33") (pintype "power_in"))
      (node (ref "U3") (pin "5") (pinfunction "GND_5") (pintype "power_in"))
    )
    (net (code "41") (name "GND_CLASSIS") (class "Default")
      (node (ref "C7") (pin "1") (pinfunction "1_1") (pintype "passive"))
      (node (ref "C8") (pin "1") (pinfunction "1_1") (pintype "passive"))
      (node (ref "C9") (pin "1") (pinfunction "1_1") (pintype "passive"))
      (node (ref "J1") (pin "S1") (pinfunction "SHIELD_1_S1") (pintype "passive"))
      (node (ref "J1") (pin "S2") (pinfunction "SHIELD_2_S2") (pintype "passive"))
      (node (ref "J1") (pin "S3") (pinfunction "SHIELD_3_S3") (pintype "passive"))
      (node (ref "J1") (pin "S4") (pinfunction "SHIELD_4_S4") (pintype "passive"))
      (node (ref "J2") (pin "S1") (pinfunction "S1_S1") (pintype "passive"))
      (node (ref "J2") (pin "S2") (pinfunction "S2_S2") (pintype "passive"))
      (node (ref "R16") (pin "2") (pinfunction "2_2") (pintype "passive"))
    )
    (net (code "42") (name "GND_USB") (class "Default")
      (node (ref "C4") (pin "2") (pinfunction "2_2") (pintype "passive"))
      (node (ref "R15") (pin "2") (pinfunction "2_2") (pintype "passive"))
    )
    (net (code "43") (name "Net-(C2-Pad2)") (class "Default")
      (node (ref "C2") (pin "2") (pinfunction "2_2") (pintype "passive"))
      (node (ref "R7") (pin "1") (pinfunction "1_1") (pintype "passive"))
      (node (ref "Y1") (pin "1") (pinfunction "1_1") (pintype "passive"))
    )
    (net (code "44") (name "Net-(C8-Pad2)") (class "Default")
      (node (ref "C8") (pin "2") (pinfunction "2_2") (pintype "passive"))
      (node (ref "R10") (pin "1") (pinfunction "1_1") (pintype "passive"))
      (node (ref "R11") (pin "1") (pinfunction "1_1") (pintype "passive"))
    )
    (net (code "45") (name "Net-(C9-Pad2)") (class "Default")
      (node (ref "C9") (pin "2") (pinfunction "2_2") (pintype "passive"))
      (node (ref "R12") (pin "1") (pinfunction "1_1") (pintype "passive"))
      (node (ref "R13") (pin "1") (pinfunction "1_1") (pintype "passive"))
    )
    (net (code "46") (name "Net-(J1-CC1)") (class "Default")
      (node (ref "J1") (pin "A5") (pinfunction "CC1_A5") (pintype "passive"))
      (node (ref "R1") (pin "1") (pinfunction "1_1") (pintype "passive"))
    )
    (net (code "47") (name "Net-(J1-CC2)") (class "Default")
      (node (ref "J1") (pin "B5") (pinfunction "CC2_B5") (pintype "passive"))
      (node (ref "R5") (pin "1") (pinfunction "1_1") (pintype "passive"))
    )
    (net (code "48") (name "Net-(J2-GND)") (class "Default")
      (node (ref "J2") (pin "6") (pinfunction "RCT_6") (pintype "passive"))
      (node (ref "J2") (pin "8") (pinfunction "GND_8") (pintype "passive"))
      (node (ref "R13") (pin "2") (pinfunction "2_2") (pintype "passive"))
    )
    (net (code "49") (name "Net-(J2-NC)") (class "Default")
      (node (ref "J2") (pin "2") (pinfunction "TCT_2") (pintype "passive"))
      (node (ref "J2") (pin "4") (pinfunction "NC_4") (pintype "passive"))
      (node (ref "R12") (pin "2") (pinfunction "2_2") (pintype "passive"))
    )
    (net (code "50") (name "Net-(LED1-A)") (class "Default")
      (node (ref "LED1") (pin "2") (pinfunction "A_2") (pintype "passive"))
      (node (ref "R2") (pin "1") (pinfunction "1_1") (pintype "passive"))
    )
    (net (code "51") (name "Net-(T1-CRD)") (class "Default")
      (node (ref "C5") (pin "2") (pinfunction "2_2") (pintype "passive"))
      (node (ref "T1") (pin "6") (pinfunction "CRD_6") (pintype "passive"))
    )
    (net (code "52") (name "Net-(T1-CRX)") (class "Default")
      (node (ref "R10") (pin "2") (pinfunction "2_2") (pintype "passive"))
      (node (ref "T1") (pin "11") (pinfunction "CRX_11") (pintype "passive"))
    )
    (net (code "53") (name "Net-(T1-CTD)") (class "Default")
      (node (ref "C6") (pin "2") (pinfunction "2_2") (pintype "passive"))
      (node (ref "T1") (pin "3") (pinfunction "CTD_3") (pintype "passive"))
    )
    (net (code "54") (name "Net-(T1-CTX)") (class "Default")
      (node (ref "R11") (pin "2") (pinfunction "2_2") (pintype "passive"))
      (node (ref "T1") (pin "14") (pinfunction "CTX_14") (pintype "passive"))
    )
    (net (code "55") (name "Net-(U1-EXRES)") (class "Default")
      (node (ref "R8") (pin "1") (pinfunction "1_1") (pintype "passive"))
      (node (ref "U1") (pin "8") (pinfunction "EXRES_8") (pintype "passive"))
    )
    (net (code "56") (name "Net-(U1-USBRBIAS)") (class "Default")
      (node (ref "R9") (pin "1") (pinfunction "1_1") (pintype "passive"))
      (node (ref "U1") (pin "16") (pinfunction "USBRBIAS_16") (pintype "passive"))
    )
    (net (code "57") (name "Net-(U1-VBUS_DET)") (class "Default")
      (node (ref "R6") (pin "2") (pinfunction "2_2") (pintype "passive"))
      (node (ref "U1") (pin "20") (pinfunction "VBUS_DET_20") (pintype "power_in"))
    )
    (net (code "58") (name "Net-(U1-XI)") (class "Default")
      (node (ref "R7") (pin "2") (pinfunction "2_2") (pintype "passive"))
      (node (ref "U1") (pin "18") (pinfunction "XI_18") (pintype "input"))
    )
    (net (code "59") (name "Net-(U1-XO)") (class "Default")
      (node (ref "C3") (pin "2") (pinfunction "2_2") (pintype "passive"))
      (node (ref "U1") (pin "19") (pinfunction "XO_19") (pintype "output"))
      (node (ref "Y1") (pin "2") (pinfunction "2_2") (pintype "passive"))
    )
    (net (code "60") (name "Net-(U1-~{RESET})") (class "Default")
      (node (ref "R14") (pin "1") (pinfunction "1_1") (pintype "passive"))
      (node (ref "U1") (pin "24") (pinfunction "~{RESET}_24") (pintype "input"))
    )
    (net (code "61") (name "Net-(U3-LDO_CAP)") (class "Default")
      (node (ref "C35") (pin "2") (pinfunction "2_2") (pintype "passive"))
      (node (ref "U3") (pin "22") (pinfunction "LDO_CAP_22") (pintype "power_in"))
    )
    (net (code "62") (name "Net-(U3-REXT)") (class "Default")
      (node (ref "R27") (pin "1") (pinfunction "1_1") (pintype "passive"))
      (node (ref "U3") (pin "10") (pinfunction "REXT_10") (pintype "passive"))
    )
    (net (code "63") (name "Net-(U3-XTAL_I{slash}CLK_IN{slash}REF_CLK)") (class "Default")
      (node (ref "C37") (pin "1") (pinfunction "1_1") (pintype "passive"))
      (node (ref "U3") (pin "8") (pinfunction "XTAL_I/CLK_IN/REF_CLK_8") (pintype "input"))
      (node (ref "Y2") (pin "1") (pinfunction "1_1") (pintype "passive"))
    )
    (net (code "64") (name "Net-(U3-XTAL_O)") (class "Default")
      (node (ref "C38") (pin "1") (pinfunction "1_1") (pintype "passive"))
      (node (ref "U3") (pin "7") (pinfunction "XTAL_O_7") (pintype "output"))
      (node (ref "Y2") (pin "2") (pinfunction "2_2") (pintype "passive"))
    )
    (net (code "65") (name "VDDCORE") (class "Default")
      (node (ref "C30") (pin "2") (pinfunction "2_2") (pintype "passive"))
      (node (ref "C31") (pin "2") (pinfunction "2_2") (pintype "passive"))
      (node (ref "C32") (pin "2") (pinfunction "2_2") (pintype "passive"))
      (node (ref "C33") (pin "2") (pinfunction "2_2") (pintype "passive"))
      (node (ref "FB2") (pin "1") (pinfunction "1_1") (pintype "passive"))
      (node (ref "FB3") (pin "1") (pinfunction "1_1") (pintype "passive"))
      (node (ref "U1") (pin "21") (pinfunction "VDDCORE_21") (pintype "power_in"))
      (node (ref "U1") (pin "50") (pinfunction "VDDCORE_50") (pintype "power_in"))
    )
    (net (code "66") (name "VDDPLL") (class "Default")
      (node (ref "C34") (pin "2") (pinfunction "2_2") (pintype "passive"))
      (node (ref "FB2") (pin "2") (pinfunction "2_2") (pintype "passive"))
      (node (ref "U1") (pin "10") (pinfunction "VDDPLL_10") (pintype "power_in"))
    )
    (net (code "67") (name "VDDUSBPLL") (class "Default")
      (node (ref "C36") (pin "2") (pinfunction "2_2") (pintype "passive"))
      (node (ref "FB3") (pin "2") (pinfunction "2_2") (pintype "passive"))
      (node (ref "U1") (pin "17") (pinfunction "VDDUSBPLL_17") (pintype "power_in"))
    )
    (net (code "68") (name "unconnected-(J1-SBU1-PadA8)") (class "Default")
      (node (ref "J1") (pin "A8") (pinfunction "SBU1_A8") (pintype "passive+no_connect"))
    )
    (net (code "69") (name "unconnected-(J1-SBU2-PadB8)") (class "Default")
      (node (ref "J1") (pin "B8") (pinfunction "SBU2_B8") (pintype "passive+no_connect"))
    )
    (net (code "70") (name "unconnected-(U1-EECLK{slash}PWR_SEL-Pad29)") (class "Default")
      (node (ref "U1") (pin "29") (pinfunction "EECLK/PWR_SEL_29") (pintype "input+no_connect"))
    )
    (net (code "71") (name "unconnected-(U1-EECS-Pad30)") (class "Default")
      (node (ref "U1") (pin "30") (pinfunction "EECS_30") (pintype "output+no_connect"))
    )
    (net (code "72") (name "unconnected-(U1-EEDI-Pad32)") (class "Default")
      (node (ref "U1") (pin "32") (pinfunction "EEDI_32") (pintype "input+no_connect"))
    )
    (net (code "73") (name "unconnected-(U1-EEDO{slash}AUTOMDIX_EN-Pad31)") (class "Default")
      (node (ref "U1") (pin "31") (pinfunction "EEDO/AUTOMDIX_EN_31") (pintype "output+no_connect"))
    )
    (net (code "74") (name "unconnected-(U1-NC-Pad7)") (class "Default")
      (node (ref "U1") (pin "7") (pinfunction "NC_7") (pintype "passive+no_connect"))
    )
    (net (code "75") (name "unconnected-(U1-NC-Pad14)") (class "Default")
      (node (ref "U1") (pin "14") (pinfunction "NC_14") (pintype "passive+no_connect"))
    )
    (net (code "76") (name "unconnected-(U1-RXN-Pad5)") (class "Default")
      (node (ref "U1") (pin "5") (pinfunction "RXN_5") (pintype "passive+no_connect"))
    )
    (net (code "77") (name "unconnected-(U1-RXP-Pad6)") (class "Default")
      (node (ref "U1") (pin "6") (pinfunction "RXP_6") (pintype "passive+no_connect"))
    )
    (net (code "78") (name "unconnected-(U1-TXN-Pad2)") (class "Default")
      (node (ref "U1") (pin "2") (pinfunction "TXN_2") (pintype "output+no_connect"))
    )
    (net (code "79") (name "unconnected-(U1-TXP-Pad3)") (class "Default")
      (node (ref "U1") (pin "3") (pinfunction "TXP_3") (pintype "output+no_connect"))
    )
  )
)
